# Atmega_secondary.net
KiCad netlist of a schematic drawn in Altium Designer
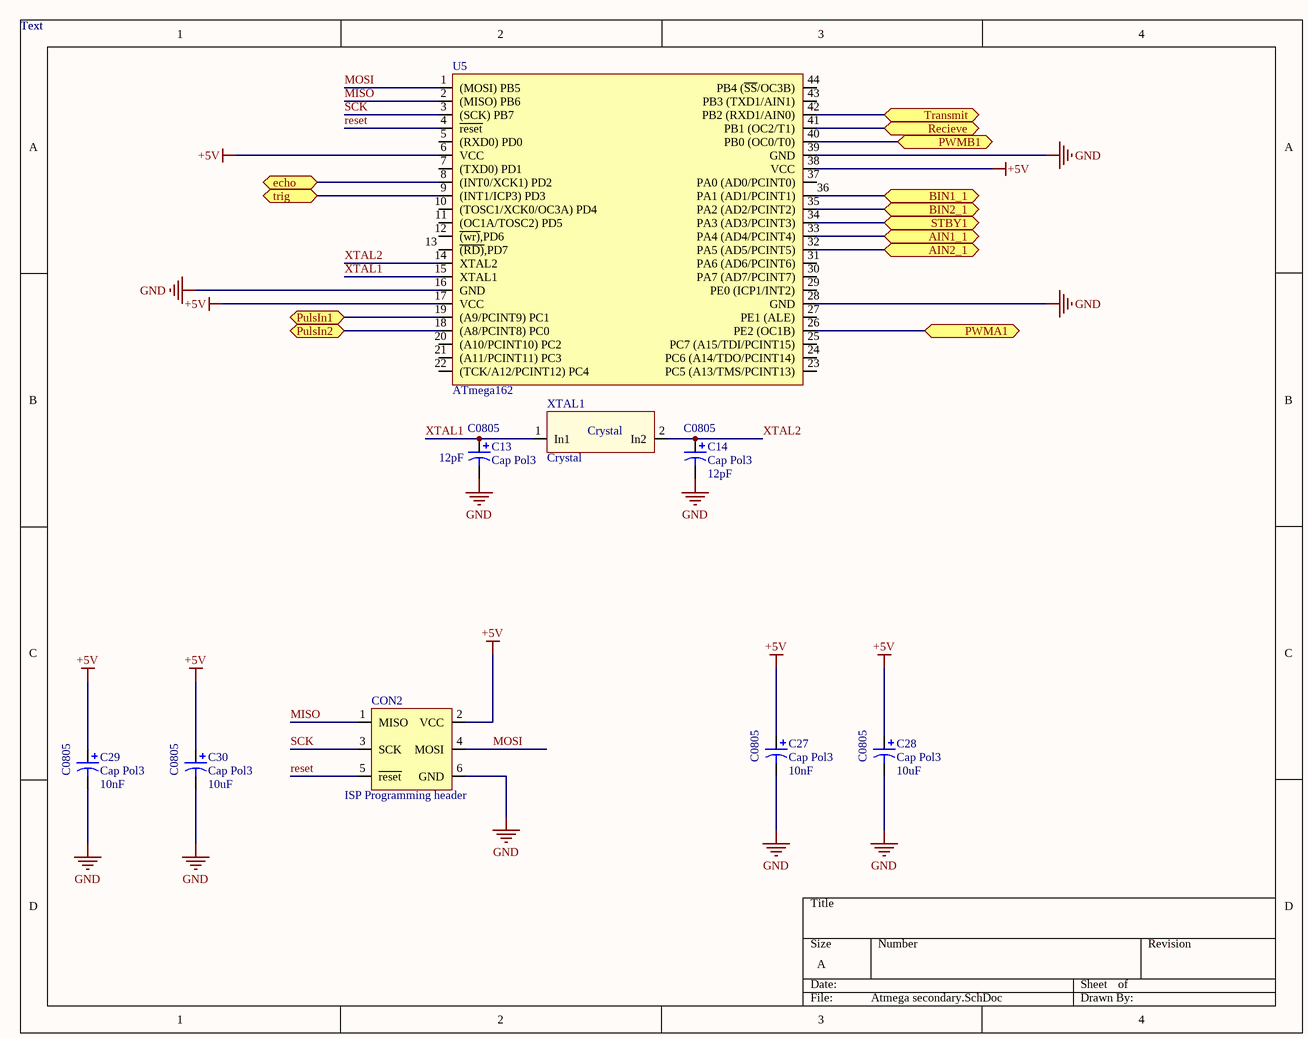
[diagram p0: Atmega secondary.SchDoc]

(export (version "E")
  (design (tool "Eeschema 10.0.6"))
  (components
    (comp (ref "C13")
      (value "Cap Pol3")
      (footprint "C0805")
      (description "Polarized Capacitor (Surface Mount)")
      (fields
        (field (name "PACKAGEREFERENCE") "C0805")
        (field (name "ALTIUM_VALUE") "12pF")
        (field (name "PUBLISHER") "Altium Limited")
      )
      (libsource (lib "Miscellaneous Devices") (part "Cap Pol3"))
    )
    (comp (ref "C14")
      (value "Cap Pol3")
      (footprint "C0805")
      (description "Polarized Capacitor (Surface Mount)")
      (fields
        (field (name "PACKAGEREFERENCE") "C0805")
        (field (name "ALTIUM_VALUE") "12pF")
        (field (name "PUBLISHER") "Altium Limited")
      )
      (libsource (lib "Miscellaneous Devices") (part "Cap Pol3"))
    )
    (comp (ref "C27")
      (value "Cap Pol3")
      (footprint "C0805")
      (description "Polarized Capacitor (Surface Mount)")
      (fields
        (field (name "PACKAGEREFERENCE") "C0805")
        (field (name "ALTIUM_VALUE") "10nF")
        (field (name "PUBLISHER") "Altium Limited")
      )
      (libsource (lib "Miscellaneous Devices") (part "Cap Pol3"))
    )
    (comp (ref "C28")
      (value "Cap Pol3")
      (footprint "C0805")
      (description "Polarized Capacitor (Surface Mount)")
      (fields
        (field (name "PACKAGEREFERENCE") "C0805")
        (field (name "ALTIUM_VALUE") "10uF")
        (field (name "PUBLISHER") "Altium Limited")
      )
      (libsource (lib "Miscellaneous Devices") (part "Cap Pol3"))
    )
    (comp (ref "C29")
      (value "Cap Pol3")
      (footprint "C0805")
      (description "Polarized Capacitor (Surface Mount)")
      (fields
        (field (name "PACKAGEREFERENCE") "C0805")
        (field (name "ALTIUM_VALUE") "10nF")
        (field (name "PUBLISHER") "Altium Limited")
      )
      (libsource (lib "Miscellaneous Devices") (part "Cap Pol3"))
    )
    (comp (ref "C30")
      (value "Cap Pol3")
      (footprint "C0805")
      (description "Polarized Capacitor (Surface Mount)")
      (fields
        (field (name "PACKAGEREFERENCE") "C0805")
        (field (name "ALTIUM_VALUE") "10uF")
        (field (name "PUBLISHER") "Altium Limited")
      )
      (libsource (lib "Miscellaneous Devices") (part "Cap Pol3"))
    )
    (comp (ref "CON2")
      (value "ISP Programming header")
      (footprint "ISP programming header")
      (libsource (lib "ATMEGA126") (part "ISP Programming header"))
    )
    (comp (ref "U5")
      (value "ATmega162")
      (footprint "ATmga162")
      (libsource (lib "ATMEGA126") (part "ATmega162"))
    )
    (comp (ref "XTAL1")
      (value "Crystal")
      (footprint "Crystal")
      (libsource (lib "ATMEGA126") (part "Crystal"))
    )
  )
  (nets
    (net (code "1") (name "+5V") (class "Default")
      (node (ref "C27") (pin "1") (pinfunction "1_1") (pintype "passive"))
      (node (ref "C28") (pin "1") (pinfunction "1_1") (pintype "passive"))
      (node (ref "C29") (pin "1") (pinfunction "1_1") (pintype "passive"))
      (node (ref "C30") (pin "1") (pinfunction "1_1") (pintype "passive"))
      (node (ref "CON2") (pin "2") (pinfunction "VCC_2") (pintype "power_in"))
      (node (ref "U5") (pin "17") (pinfunction "VCC_17") (pintype "passive"))
      (node (ref "U5") (pin "38") (pinfunction "VCC_38") (pintype "passive"))
      (node (ref "U5") (pin "6") (pinfunction "VCC_6") (pintype "passive"))
    )
    (net (code "2") (name "/AIN1_1") (class "Default")
      (node (ref "U5") (pin "33") (pinfunction "PA4_(AD4/PCINT4)_33") (pintype "passive"))
    )
    (net (code "3") (name "/AIN2_1") (class "Default")
      (node (ref "U5") (pin "32") (pinfunction "PA5_(AD5/PCINT5)_32") (pintype "passive"))
    )
    (net (code "4") (name "/BIN1_1") (class "Default")
      (node (ref "U5") (pin "36") (pinfunction "PA1_(AD1/PCINT1)_36") (pintype "passive"))
    )
    (net (code "5") (name "/BIN2_1") (class "Default")
      (node (ref "U5") (pin "35") (pinfunction "PA2_(AD2/PCINT2)_35") (pintype "passive"))
    )
    (net (code "6") (name "/MISO") (class "Default")
      (node (ref "CON2") (pin "1") (pinfunction "MISO_1") (pintype "passive"))
      (node (ref "U5") (pin "2") (pinfunction "(MISO)_PB6_2") (pintype "passive"))
    )
    (net (code "7") (name "/MOSI") (class "Default")
      (node (ref "CON2") (pin "4") (pinfunction "MOSI_4") (pintype "passive"))
      (node (ref "U5") (pin "1") (pinfunction "(MOSI)_PB5_1") (pintype "passive"))
    )
    (net (code "8") (name "/PWMA1") (class "Default")
      (node (ref "U5") (pin "26") (pinfunction "PE2_(OC1B)_26") (pintype "passive"))
    )
    (net (code "9") (name "/PWMB1") (class "Default")
      (node (ref "U5") (pin "40") (pinfunction "PB0_(OC0/T0)_40") (pintype "passive"))
    )
    (net (code "10") (name "/PulsIn1") (class "Default")
      (node (ref "U5") (pin "19") (pinfunction "(A9/PCINT9)_PC1_19") (pintype "passive"))
    )
    (net (code "11") (name "/PulsIn2") (class "Default")
      (node (ref "U5") (pin "18") (pinfunction "(A8/PCINT8)_PC0_18") (pintype "passive"))
    )
    (net (code "12") (name "/Recieve") (class "Default")
      (node (ref "U5") (pin "41") (pinfunction "PB1_(OC2/T1)_41") (pintype "passive"))
    )
    (net (code "13") (name "/SCK") (class "Default")
      (node (ref "CON2") (pin "3") (pinfunction "SCK_3") (pintype "passive"))
      (node (ref "U5") (pin "3") (pinfunction "(SCK)_PB7_3") (pintype "passive"))
    )
    (net (code "14") (name "/STBY1") (class "Default")
      (node (ref "U5") (pin "34") (pinfunction "PA3_(AD3/PCINT3)_34") (pintype "passive"))
    )
    (net (code "15") (name "/Transmit") (class "Default")
      (node (ref "U5") (pin "42") (pinfunction "PB2_(RXD1/AIN0)_42") (pintype "passive"))
    )
    (net (code "16") (name "/XTAL1") (class "Default")
      (node (ref "C13") (pin "1") (pinfunction "1_1") (pintype "passive"))
      (node (ref "U5") (pin "15") (pinfunction "XTAL1_15") (pintype "passive"))
      (node (ref "XTAL1") (pin "1") (pinfunction "In1_1") (pintype "passive"))
    )
    (net (code "17") (name "/XTAL2") (class "Default")
      (node (ref "C14") (pin "1") (pinfunction "1_1") (pintype "passive"))
      (node (ref "U5") (pin "14") (pinfunction "XTAL2_14") (pintype "passive"))
      (node (ref "XTAL1") (pin "2") (pinfunction "In2_2") (pintype "passive"))
    )
    (net (code "18") (name "/echo") (class "Default")
      (node (ref "U5") (pin "8") (pinfunction "(INT0/XCK1)_PD2_8") (pintype "passive"))
    )
    (net (code "19") (name "/reset") (class "Default")
      (node (ref "CON2") (pin "5") (pinfunction "~{reset}_5") (pintype "passive"))
      (node (ref "U5") (pin "4") (pinfunction "~{reset}_4") (pintype "passive"))
    )
    (net (code "20") (name "/trig") (class "Default")
      (node (ref "U5") (pin "9") (pinfunction "(INT1/ICP3)_PD3_9") (pintype "passive"))
    )
    (net (code "21") (name "GND") (class "Default")
      (node (ref "C13") (pin "2") (pinfunction "2_2") (pintype "passive"))
      (node (ref "C14") (pin "2") (pinfunction "2_2") (pintype "passive"))
      (node (ref "C27") (pin "2") (pinfunction "2_2") (pintype "passive"))
      (node (ref "C28") (pin "2") (pinfunction "2_2") (pintype "passive"))
      (node (ref "C29") (pin "2") (pinfunction "2_2") (pintype "passive"))
      (node (ref "C30") (pin "2") (pinfunction "2_2") (pintype "passive"))
      (node (ref "CON2") (pin "6") (pinfunction "GND_6") (pintype "power_in"))
      (node (ref "U5") (pin "16") (pinfunction "GND_16") (pintype "passive"))
      (node (ref "U5") (pin "28") (pinfunction "GND_28") (pintype "passive"))
      (node (ref "U5") (pin "39") (pinfunction "GND_39") (pintype "passive"))
    )
    (net (code "22") (name "unconnected-(U5-(A10{slash}PCINT10)_PC2-Pad20)") (class "Default")
      (node (ref "U5") (pin "20") (pinfunction "(A10/PCINT10)_PC2_20") (pintype "passive"))
    )
    (net (code "23") (name "unconnected-(U5-(A11{slash}PCINT11)_PC3-Pad21)") (class "Default")
      (node (ref "U5") (pin "21") (pinfunction "(A11/PCINT11)_PC3_21") (pintype "passive"))
    )
    (net (code "24") (name "unconnected-(U5-(OC1A{slash}TOSC2)_PD5-Pad11)") (class "Default")
      (node (ref "U5") (pin "11") (pinfunction "(OC1A/TOSC2)_PD5_11") (pintype "passive"))
    )
    (net (code "25") (name "unconnected-(U5-(RXD0)_PD0-Pad5)") (class "Default")
      (node (ref "U5") (pin "5") (pinfunction "(RXD0)_PD0_5") (pintype "passive"))
    )
    (net (code "26") (name "unconnected-(U5-(TCK{slash}A12{slash}PCINT12)_PC4-Pad22)") (class "Default")
      (node (ref "U5") (pin "22") (pinfunction "(TCK/A12/PCINT12)_PC4_22") (pintype "passive"))
    )
    (net (code "27") (name "unconnected-(U5-(TOSC1{slash}XCK0{slash}OC3A)_PD4-Pad10)") (class "Default")
      (node (ref "U5") (pin "10") (pinfunction "(TOSC1/XCK0/OC3A)_PD4_10") (pintype "passive"))
    )
    (net (code "28") (name "unconnected-(U5-(TXD0)_PD1-Pad7)") (class "Default")
      (node (ref "U5") (pin "7") (pinfunction "(TXD0)_PD1_7") (pintype "passive"))
    )
    (net (code "29") (name "unconnected-(U5-PA0_(AD0{slash}PCINT0)-Pad37)") (class "Default")
      (node (ref "U5") (pin "37") (pinfunction "PA0_(AD0/PCINT0)_37") (pintype "passive"))
    )
    (net (code "30") (name "unconnected-(U5-PA6_(AD6{slash}PCINT6)-Pad31)") (class "Default")
      (node (ref "U5") (pin "31") (pinfunction "PA6_(AD6/PCINT6)_31") (pintype "passive"))
    )
    (net (code "31") (name "unconnected-(U5-PA7_(AD7{slash}PCINT7)-Pad30)") (class "Default")
      (node (ref "U5") (pin "30") (pinfunction "PA7_(AD7/PCINT7)_30") (pintype "passive"))
    )
    (net (code "32") (name "unconnected-(U5-PB3_(TXD1{slash}AIN1)-Pad43)") (class "Default")
      (node (ref "U5") (pin "43") (pinfunction "PB3_(TXD1/AIN1)_43") (pintype "passive"))
    )
    (net (code "33") (name "unconnected-(U5-PB4_(~{SS}{slash}OC3B)-Pad44)") (class "Default")
      (node (ref "U5") (pin "44") (pinfunction "PB4_(~{SS}/OC3B)_44") (pintype "passive"))
    )
    (net (code "34") (name "unconnected-(U5-PC5_(A13{slash}TMS{slash}PCINT13)-Pad23)") (class "Default")
      (node (ref "U5") (pin "23") (pinfunction "PC5_(A13/TMS/PCINT13)_23") (pintype "passive"))
    )
    (net (code "35") (name "unconnected-(U5-PC6_(A14{slash}TDO{slash}PCINT14)-Pad24)") (class "Default")
      (node (ref "U5") (pin "24") (pinfunction "PC6_(A14/TDO/PCINT14)_24") (pintype "passive"))
    )
    (net (code "36") (name "unconnected-(U5-PC7_(A15{slash}TDI{slash}PCINT15)-Pad25)") (class "Default")
      (node (ref "U5") (pin "25") (pinfunction "PC7_(A15/TDI/PCINT15)_25") (pintype "passive"))
    )
    (net (code "37") (name "unconnected-(U5-PE0_(ICP1{slash}INT2)-Pad29)") (class "Default")
      (node (ref "U5") (pin "29") (pinfunction "PE0_(ICP1/INT2)_29") (pintype "passive"))
    )
    (net (code "38") (name "unconnected-(U5-PE1_(ALE)-Pad27)") (class "Default")
      (node (ref "U5") (pin "27") (pinfunction "PE1_(ALE)_27") (pintype "passive"))
    )
    (net (code "39") (name "unconnected-(U5-~{(RD)},PD7-Pad13)") (class "Default")
      (node (ref "U5") (pin "13") (pinfunction "~{(RD)},PD7_13") (pintype "passive"))
    )
    (net (code "40") (name "unconnected-(U5-~{(wr)},PD6-Pad12)") (class "Default")
      (node (ref "U5") (pin "12") (pinfunction "~{(wr)},PD6_12") (pintype "passive"))
    )
  )
)
